# 5_BATT_3V3.net
KiCad netlist of a schematic drawn in Altium Designer
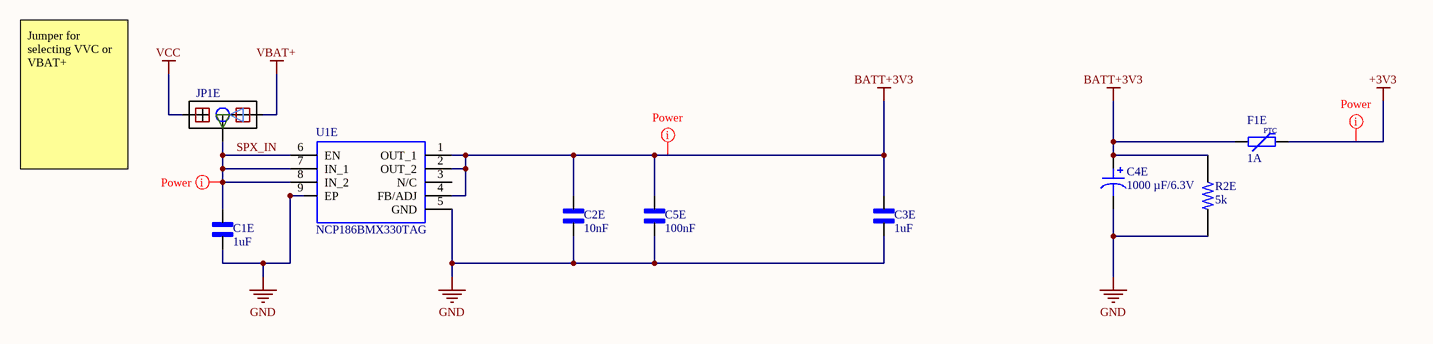
[diagram p0: 5_BATT+3V3.SchDoc]

(export (version "E")
  (design (tool "Eeschema 10.0.6"))
  (components
    (comp (ref "C1E")
      (value "1uF")
      (footprint "C-0603")
      (description "Ceramic Capacitor 16V 0603 (1608 Metric)")
      (fields (field (name "MP") "C0603C104J4RAC") (field (name "MF") "KEMET"))
      (libsource (lib "ESP-12F_WLED_IOT_LIPO") (part "C-0603"))
    )
    (comp (ref "C2E")
      (value "10nF")
      (footprint "C-0603")
      (description "Ceramic Capacitor 16V 0603 (1608 Metric)")
      (fields (field (name "MP") "C0603C104J4RAC") (field (name "MF") "KEMET"))
      (libsource (lib "ESP-12F_WLED_IOT_LIPO") (part "C-0603"))
    )
    (comp (ref "C3E")
      (value "1uF")
      (footprint "C-0603")
      (description "Ceramic Capacitor 16V 0603 (1608 Metric)")
      (fields (field (name "MP") "C0603C104J4RAC") (field (name "MF") "KEMET"))
      (libsource (lib "ESP-12F_WLED_IOT_LIPO") (part "C-0603"))
    )
    (comp (ref "C4E")
      (value "1000 µF/6.3V")
      (footprint "CAP AL TH D8 L3.5 H12.5")
      (description "CAP ALUM 1000UF 20% 6.3V RADIAL")
      (fields
        (field (name "PART NUMBER") "ECA-0JHG102")
        (field (name "MANUFACTURER") "Panasonic Electronic Components")
      )
      (libsource (lib "ESP-12F_WLED_IOT_LIPO") (part "Polarised Capacitor"))
    )
    (comp (ref "C5E")
      (value "100nF")
      (footprint "C-0603")
      (description "Ceramic Capacitor 16V 0603 (1608 Metric)")
      (fields (field (name "MP") "C0603C104J4RAC") (field (name "MF") "KEMET"))
      (libsource (lib "ESP-12F_WLED_IOT_LIPO") (part "C-0603"))
    )
    (comp (ref "F1E")
      (value "1A")
      (footprint "FUSE_1206")
      (description "Fuse PPTC SMD 1206")
      (libsource (lib "ESP-12F_WLED_IOT_LIPO") (part "FUSE_PPTC_1206"))
    )
    (comp (ref "JP1E")
      (value "Solder Pad")
      (footprint "Solder_Pad_3_Pin_NC_Medium")
      (description "Solder Pad 3 Pin NC 1.016 mm Pitch")
      (libsource (lib "ESP-12F_WLED_IOT_LIPO") (part "Solder_Pad_3_Pin_NC_Medium"))
    )
    (comp (ref "R2E")
      (value "5k")
      (footprint "R-0603")
      (description "0603")
      (fields (field (name "MP") "2-1623703-0") (field (name "TOLERANCE") "1%"))
      (libsource (lib "ESP-12F_WLED_IOT_LIPO") (part "R-0603"))
    )
    (comp (ref "U1E")
      (value "NCP186BMX330TAG")
      (footprint "NCP186AMX330TAG")
      (description "LDO Voltage Regulators FAST TRANSIENT RESPO")
      (fields (field (name "MOUSER PART NUMBER") "863-NCP186BMX330TAG"))
      (libsource (lib "ESP-12F_WLED_IOT_LIPO") (part "NCP186BMX330TAG"))
    )
  )
  (nets
    (net (code "1") (name "+3V3") (class "Default")
      (node (ref "F1E") (pin "2") (pinfunction "2_2") (pintype "passive"))
    )
    (net (code "2") (name "/SPX_IN") (class "Default")
      (node (ref "C1E") (pin "2") (pinfunction "2_2") (pintype "passive"))
      (node (ref "JP1E") (pin "2") (pinfunction "2_2") (pintype "passive"))
      (node (ref "U1E") (pin "6") (pinfunction "EN_6") (pintype "passive"))
      (node (ref "U1E") (pin "7") (pinfunction "IN_1_7") (pintype "passive"))
      (node (ref "U1E") (pin "8") (pinfunction "IN_2_8") (pintype "passive"))
    )
    (net (code "3") (name "BATT+3V3") (class "Default")
      (node (ref "C2E") (pin "2") (pinfunction "2_2") (pintype "passive"))
      (node (ref "C3E") (pin "2") (pinfunction "2_2") (pintype "passive"))
      (node (ref "C4E") (pin "1") (pinfunction "1_1") (pintype "passive"))
      (node (ref "C5E") (pin "2") (pinfunction "2_2") (pintype "passive"))
      (node (ref "F1E") (pin "1") (pinfunction "1_1") (pintype "passive"))
      (node (ref "R2E") (pin "1") (pinfunction "1_1") (pintype "passive"))
      (node (ref "U1E") (pin "1") (pinfunction "OUT_1_1") (pintype "passive"))
      (node (ref "U1E") (pin "2") (pinfunction "OUT_2_2") (pintype "passive"))
      (node (ref "U1E") (pin "4") (pinfunction "FB/ADJ_4") (pintype "passive"))
    )
    (net (code "4") (name "GND") (class "Default")
      (node (ref "C1E") (pin "1") (pinfunction "1_1") (pintype "passive"))
      (node (ref "C2E") (pin "1") (pinfunction "1_1") (pintype "passive"))
      (node (ref "C3E") (pin "1") (pinfunction "1_1") (pintype "passive"))
      (node (ref "C4E") (pin "2") (pinfunction "2_2") (pintype "passive"))
      (node (ref "C5E") (pin "1") (pinfunction "1_1") (pintype "passive"))
      (node (ref "R2E") (pin "2") (pinfunction "2_2") (pintype "passive"))
      (node (ref "U1E") (pin "5") (pinfunction "GND_5") (pintype "passive"))
      (node (ref "U1E") (pin "9") (pinfunction "EP_9") (pintype "passive"))
    )
    (net (code "5") (name "VBAT+") (class "Default")
      (node (ref "JP1E") (pin "1") (pinfunction "1_1") (pintype "passive"))
    )
    (net (code "6") (name "VCC") (class "Default")
      (node (ref "JP1E") (pin "3") (pinfunction "3_3") (pintype "passive"))
    )
    (net (code "7") (name "unconnected-(U1E-N{slash}C-Pad3)") (class "Default")
      (node (ref "U1E") (pin "3") (pinfunction "N/C_3") (pintype "passive"))
    )
  )
)
